# pressure_sensor.net
KiCad netlist of a schematic drawn in Altium Designer
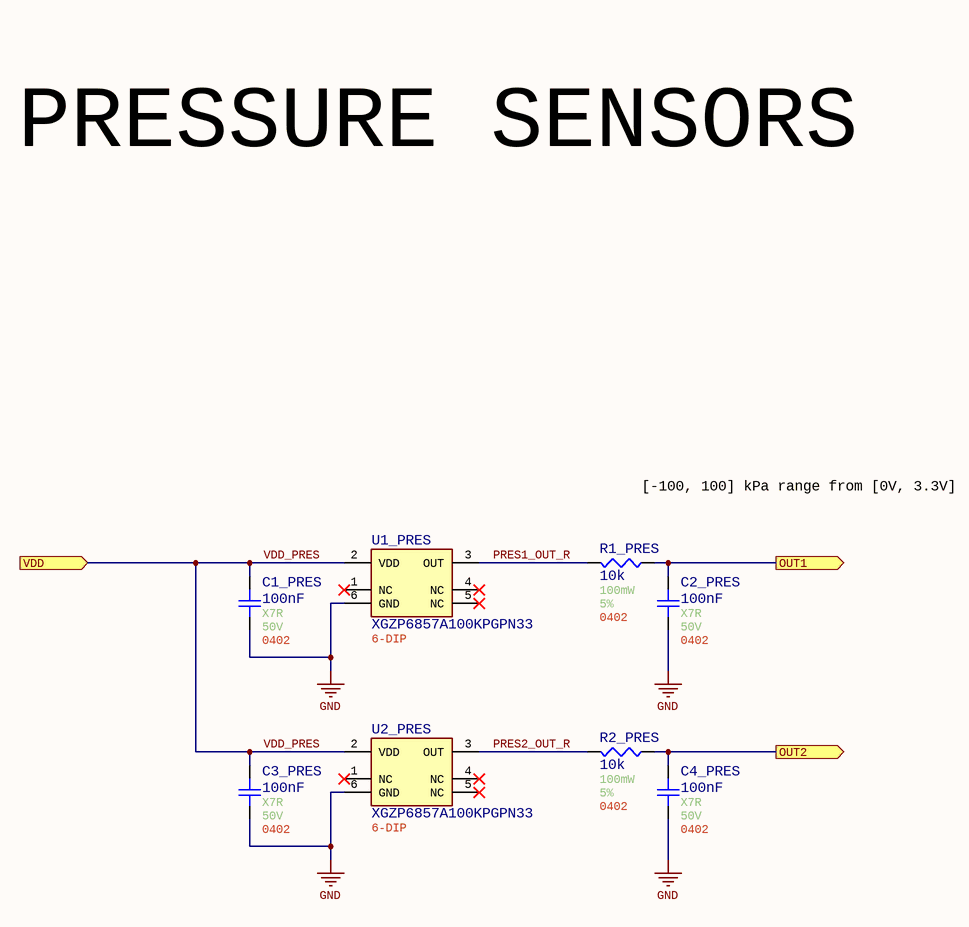
[diagram p0: pressure_sensor.SchDoc]

(export (version "E")
  (design (tool "Eeschema 10.0.6"))
  (components
    (comp (ref "C1_PRES")
      (value "100nF")
      (footprint "Generic 0402 capacitor")
      (fields
        (field (name "TEMPERATURE COEFFICIENT") "X7R")
        (field (name "VOLTAGE RATING") "50V")
        (field (name "CASE/PACKAGE") "0402")
        (field (name "TOLERANCE") "10%")
        (field (name "Comment") "GRT155R71H104KE01D")
      )
      (libsource (lib "Raise Robotics") (part "Unpolarized Capacitor"))
    )
    (comp (ref "C2_PRES")
      (value "100nF")
      (footprint "Generic 0402 capacitor")
      (fields
        (field (name "TEMPERATURE COEFFICIENT") "X7R")
        (field (name "VOLTAGE RATING") "50V")
        (field (name "CASE/PACKAGE") "0402")
        (field (name "TOLERANCE") "10%")
        (field (name "Comment") "GRT155R71H104KE01D")
      )
      (libsource (lib "Raise Robotics") (part "Unpolarized Capacitor"))
    )
    (comp (ref "C3_PRES")
      (value "100nF")
      (footprint "Generic 0402 capacitor")
      (fields
        (field (name "TEMPERATURE COEFFICIENT") "X7R")
        (field (name "VOLTAGE RATING") "50V")
        (field (name "CASE/PACKAGE") "0402")
        (field (name "TOLERANCE") "10%")
        (field (name "Comment") "GRT155R71H104KE01D")
      )
      (libsource (lib "Raise Robotics") (part "Unpolarized Capacitor"))
    )
    (comp (ref "C4_PRES")
      (value "100nF")
      (footprint "Generic 0402 capacitor")
      (fields
        (field (name "TEMPERATURE COEFFICIENT") "X7R")
        (field (name "VOLTAGE RATING") "50V")
        (field (name "CASE/PACKAGE") "0402")
        (field (name "TOLERANCE") "10%")
        (field (name "Comment") "GRT155R71H104KE01D")
      )
      (libsource (lib "Raise Robotics") (part "Unpolarized Capacitor"))
    )
    (comp (ref "R1_PRES")
      (value "10k")
      (footprint "Generic 0402 Resistor")
      (description "Res Thick Film 0402 10K Ohm 5% 1/10W ±200ppm/°C Molded SMD Punched Carrier T/R")
      (fields
        (field (name "POWER") "100mW")
        (field (name "TOLERANCE") "5%")
        (field (name "CASE/PACKAGE") "0402")
        (field (name "Comment") "ERJ-2GEJ103X")
      )
      (libsource (lib "Raise Robotics") (part "Resistor"))
    )
    (comp (ref "R2_PRES")
      (value "10k")
      (footprint "Generic 0402 Resistor")
      (description "Res Thick Film 0402 10K Ohm 5% 1/10W ±200ppm/°C Molded SMD Punched Carrier T/R")
      (fields
        (field (name "POWER") "100mW")
        (field (name "TOLERANCE") "5%")
        (field (name "CASE/PACKAGE") "0402")
        (field (name "Comment") "ERJ-2GEJ103X")
      )
      (libsource (lib "Raise Robotics") (part "Resistor"))
    )
    (comp (ref "U1_PRES")
      (value "XGZP6857A100KPGPN33")
      (footprint "6-DIP_XGZP6857")
      (description "Pressure Sensor 14.5PSI(-100 - 100)kPa")
      (fields (field (name "CASE/PACKAGE") "6-DIP"))
      (libsource (lib "Raise Robotics") (part "XGZP6857A"))
    )
    (comp (ref "U2_PRES")
      (value "XGZP6857A100KPGPN33")
      (footprint "6-DIP_XGZP6857")
      (description "Pressure Sensor 14.5PSI(-100 - 100)kPa")
      (fields (field (name "CASE/PACKAGE") "6-DIP"))
      (libsource (lib "Raise Robotics") (part "XGZP6857A"))
    )
  )
  (nets
    (net (code "1") (name "/OUT1") (class "Default")
      (node (ref "C2_PRES") (pin "2") (pinfunction "2_2") (pintype "passive"))
      (node (ref "R1_PRES") (pin "1") (pinfunction "1_1") (pintype "passive"))
    )
    (net (code "2") (name "/OUT2") (class "Default")
      (node (ref "C4_PRES") (pin "2") (pinfunction "2_2") (pintype "passive"))
      (node (ref "R2_PRES") (pin "1") (pinfunction "1_1") (pintype "passive"))
    )
    (net (code "3") (name "/PRES1_OUT_R") (class "Default")
      (node (ref "R1_PRES") (pin "2") (pinfunction "2_2") (pintype "passive"))
      (node (ref "U1_PRES") (pin "3") (pinfunction "OUT_3") (pintype "passive"))
    )
    (net (code "4") (name "/PRES2_OUT_R") (class "Default")
      (node (ref "R2_PRES") (pin "2") (pinfunction "2_2") (pintype "passive"))
      (node (ref "U2_PRES") (pin "3") (pinfunction "OUT_3") (pintype "passive"))
    )
    (net (code "5") (name "/VDD_PRES") (class "Default")
      (node (ref "C1_PRES") (pin "2") (pinfunction "2_2") (pintype "passive"))
      (node (ref "C3_PRES") (pin "2") (pinfunction "2_2") (pintype "passive"))
      (node (ref "U1_PRES") (pin "2") (pinfunction "VDD_2") (pintype "passive"))
      (node (ref "U2_PRES") (pin "2") (pinfunction "VDD_2") (pintype "passive"))
    )
    (net (code "6") (name "GND") (class "Default")
      (node (ref "C1_PRES") (pin "1") (pinfunction "1_1") (pintype "passive"))
      (node (ref "C2_PRES") (pin "1") (pinfunction "1_1") (pintype "passive"))
      (node (ref "C3_PRES") (pin "1") (pinfunction "1_1") (pintype "passive"))
      (node (ref "C4_PRES") (pin "1") (pinfunction "1_1") (pintype "passive"))
      (node (ref "U1_PRES") (pin "6") (pinfunction "GND_6") (pintype "passive"))
      (node (ref "U2_PRES") (pin "6") (pinfunction "GND_6") (pintype "passive"))
    )
    (net (code "7") (name "unconnected-(U1_PRES-NC-Pad1)") (class "Default")
      (node (ref "U1_PRES") (pin "1") (pinfunction "NC_1") (pintype "passive+no_connect"))
    )
    (net (code "8") (name "unconnected-(U1_PRES-NC-Pad4)") (class "Default")
      (node (ref "U1_PRES") (pin "4") (pinfunction "NC_4") (pintype "passive+no_connect"))
    )
    (net (code "9") (name "unconnected-(U1_PRES-NC-Pad5)") (class "Default")
      (node (ref "U1_PRES") (pin "5") (pinfunction "NC_5") (pintype "passive+no_connect"))
    )
    (net (code "10") (name "unconnected-(U2_PRES-NC-Pad1)") (class "Default")
      (node (ref "U2_PRES") (pin "1") (pinfunction "NC_1") (pintype "passive+no_connect"))
    )
    (net (code "11") (name "unconnected-(U2_PRES-NC-Pad4)") (class "Default")
      (node (ref "U2_PRES") (pin "4") (pinfunction "NC_4") (pintype "passive+no_connect"))
    )
    (net (code "12") (name "unconnected-(U2_PRES-NC-Pad5)") (class "Default")
      (node (ref "U2_PRES") (pin "5") (pinfunction "NC_5") (pintype "passive+no_connect"))
    )
  )
)
